# FEU-102-1_part4.net
KiCad netlist of a schematic drawn in Altium Designer
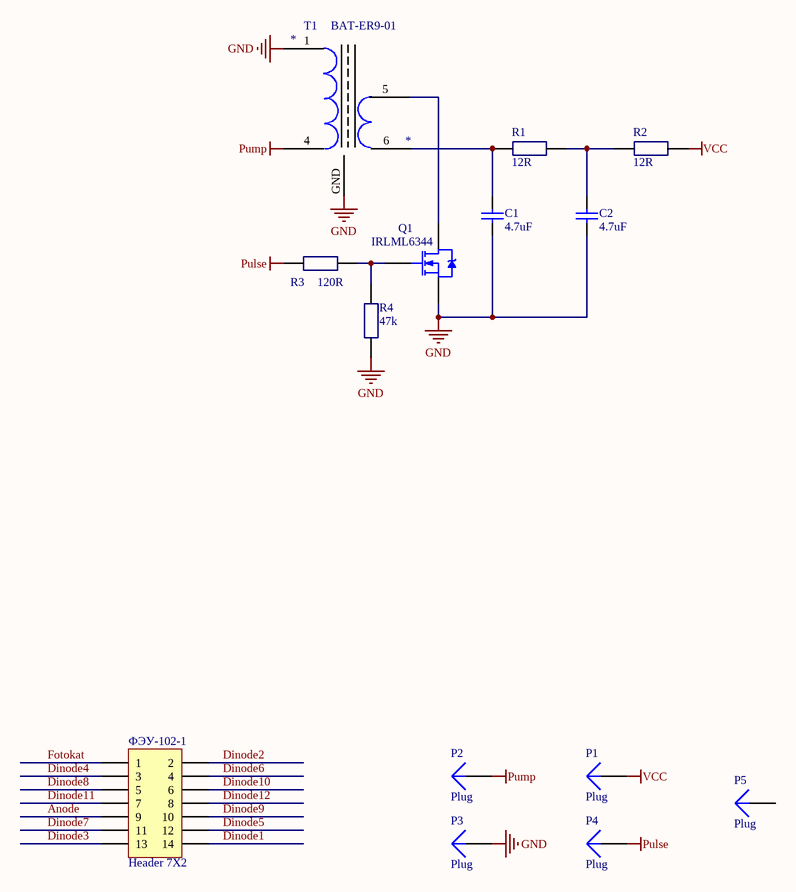
[diagram p0: FEU-102-1_part4.SchDoc]

(export (version "E")
  (design (tool "Eeschema 10.0.6"))
  (components
    (comp (ref "C1")
      (value "4.7uF")
      (footprint "Miscellaneous Devices:C1206")
      (description "Capacitor (Semiconductor SIM Model)")
      (fields (field (name "PUBLISHER") "Altium Limited"))
      (libsource (lib "Miscellaneous Devices") (part "Cap Semi"))
    )
    (comp (ref "C2")
      (value "4.7uF")
      (footprint "Miscellaneous Devices:C1206")
      (description "Capacitor (Semiconductor SIM Model)")
      (fields (field (name "PUBLISHER") "Altium Limited"))
      (libsource (lib "Miscellaneous Devices") (part "Cap Semi"))
    )
    (comp (ref "P1")
      (value "Plug")
      (footprint "PIN1")
      (fields (field (name "PUBLISHER") "Altium Limited"))
      (libsource (lib "Miscellaneous Connectors") (part "Plug"))
    )
    (comp (ref "P2")
      (value "Plug")
      (footprint "PIN1")
      (fields (field (name "PUBLISHER") "Altium Limited"))
      (libsource (lib "Miscellaneous Connectors") (part "Plug"))
    )
    (comp (ref "P3")
      (value "Plug")
      (footprint "PIN1")
      (fields (field (name "PUBLISHER") "Altium Limited"))
      (libsource (lib "Miscellaneous Connectors") (part "Plug"))
    )
    (comp (ref "P4")
      (value "Plug")
      (footprint "PIN1")
      (fields (field (name "PUBLISHER") "Altium Limited"))
      (libsource (lib "Miscellaneous Connectors") (part "Plug"))
    )
    (comp (ref "P5")
      (value "Plug")
      (footprint "PIN1")
      (fields (field (name "PUBLISHER") "Altium Limited"))
      (libsource (lib "Miscellaneous Connectors") (part "Plug"))
    )
    (comp (ref "Q1")
      (value "IRLML6344")
      (footprint "SOT-23_N")
      (description "HEXFET Power MOSFET")
      (fields (field (name "PUBLISHER") "Altium Limited"))
      (libsource (lib "IR Discrete MOSFET - Power") (part "IRLML2402"))
    )
    (comp (ref "R1")
      (value "12R")
      (footprint "1608[0603]_RES")
      (libsource (lib "Микрон-3") (part "Resistor 0805"))
    )
    (comp (ref "R2")
      (value "12R")
      (footprint "1608[0603]_RES")
      (libsource (lib "Микрон-3") (part "Resistor 0805"))
    )
    (comp (ref "R3")
      (value "120R")
      (footprint "1608[0603]_RES")
      (libsource (lib "Микрон-3") (part "Resistor 0805"))
    )
    (comp (ref "R4")
      (value "47k")
      (footprint "1608[0603]_RES")
      (libsource (lib "Микрон-3") (part "Resistor 0805"))
    )
    (comp (ref "T1")
      (value "BAT-ER9-01")
      (footprint "Epcos ER9.5/5")
      (libsource (lib "My SCH library") (part "Epcos ER9.5/5"))
    )
    (comp (ref "ФЭУ-102-1")
      (value "Header 7X2")
      (footprint "ФЭУ-102")
      (description "Header, 7-Pin, Dual row")
      (fields (field (name "PUBLISHER") "Altium Limited"))
      (libsource (lib "Miscellaneous Connectors") (part "Header 7X2"))
    )
  )
  (nets
    (net (code "1") (name "/Anode") (class "Default")
      (node (ref "ФЭУ-102-1") (pin "9") (pinfunction "9_9") (pintype "passive"))
    )
    (net (code "2") (name "/Dinode1") (class "Default")
      (node (ref "ФЭУ-102-1") (pin "14") (pinfunction "14_14") (pintype "passive"))
    )
    (net (code "3") (name "/Dinode2") (class "Default")
      (node (ref "ФЭУ-102-1") (pin "2") (pinfunction "2_2") (pintype "passive"))
    )
    (net (code "4") (name "/Dinode3") (class "Default")
      (node (ref "ФЭУ-102-1") (pin "13") (pinfunction "13_13") (pintype "passive"))
    )
    (net (code "5") (name "/Dinode4") (class "Default")
      (node (ref "ФЭУ-102-1") (pin "3") (pinfunction "3_3") (pintype "passive"))
    )
    (net (code "6") (name "/Dinode5") (class "Default")
      (node (ref "ФЭУ-102-1") (pin "12") (pinfunction "12_12") (pintype "passive"))
    )
    (net (code "7") (name "/Dinode6") (class "Default")
      (node (ref "ФЭУ-102-1") (pin "4") (pinfunction "4_4") (pintype "passive"))
    )
    (net (code "8") (name "/Dinode7") (class "Default")
      (node (ref "ФЭУ-102-1") (pin "11") (pinfunction "11_11") (pintype "passive"))
    )
    (net (code "9") (name "/Dinode8") (class "Default")
      (node (ref "ФЭУ-102-1") (pin "5") (pinfunction "5_5") (pintype "passive"))
    )
    (net (code "10") (name "/Dinode9") (class "Default")
      (node (ref "ФЭУ-102-1") (pin "10") (pinfunction "10_10") (pintype "passive"))
    )
    (net (code "11") (name "/Dinode10") (class "Default")
      (node (ref "ФЭУ-102-1") (pin "6") (pinfunction "6_6") (pintype "passive"))
    )
    (net (code "12") (name "/Dinode11") (class "Default")
      (node (ref "ФЭУ-102-1") (pin "7") (pinfunction "7_7") (pintype "passive"))
    )
    (net (code "13") (name "/Dinode12") (class "Default")
      (node (ref "ФЭУ-102-1") (pin "8") (pinfunction "8_8") (pintype "passive"))
    )
    (net (code "14") (name "/Fotokat") (class "Default")
      (node (ref "ФЭУ-102-1") (pin "1") (pinfunction "1_1") (pintype "passive"))
    )
    (net (code "15") (name "GND") (class "Default")
      (node (ref "C1") (pin "2") (pinfunction "2_2") (pintype "passive"))
      (node (ref "C2") (pin "2") (pinfunction "2_2") (pintype "passive"))
      (node (ref "P3") (pin "1") (pinfunction "1_1") (pintype "passive"))
      (node (ref "Q1") (pin "2") (pinfunction "S_2") (pintype "passive"))
      (node (ref "R4") (pin "1") (pinfunction "A_1") (pintype "passive"))
      (node (ref "T1") (pin "1") (pinfunction "1_1") (pintype "passive"))
      (node (ref "T1") (pin "GND") (pinfunction "GND_GND") (pintype "passive"))
    )
    (net (code "16") (name "Net-(Q1-D)") (class "Default")
      (node (ref "Q1") (pin "3") (pinfunction "D_3") (pintype "passive"))
      (node (ref "T1") (pin "5") (pinfunction "5_5") (pintype "passive"))
    )
    (net (code "17") (name "Net-(Q1-G)") (class "Default")
      (node (ref "Q1") (pin "1") (pinfunction "G_1") (pintype "passive"))
      (node (ref "R3") (pin "1") (pinfunction "A_1") (pintype "passive"))
      (node (ref "R4") (pin "2") (pinfunction "2_2") (pintype "passive"))
    )
    (net (code "18") (name "Net-(R1-A)") (class "Default")
      (node (ref "C1") (pin "1") (pinfunction "1_1") (pintype "passive"))
      (node (ref "R1") (pin "1") (pinfunction "A_1") (pintype "passive"))
      (node (ref "T1") (pin "6") (pintype "passive"))
    )
    (net (code "19") (name "Net-(R2-A)") (class "Default")
      (node (ref "C2") (pin "1") (pinfunction "1_1") (pintype "passive"))
      (node (ref "R1") (pin "2") (pinfunction "2_2") (pintype "passive"))
      (node (ref "R2") (pin "1") (pinfunction "A_1") (pintype "passive"))
    )
    (net (code "20") (name "Pulse") (class "Default")
      (node (ref "P4") (pin "1") (pinfunction "1_1") (pintype "passive"))
      (node (ref "R3") (pin "2") (pinfunction "2_2") (pintype "passive"))
    )
    (net (code "21") (name "Pump") (class "Default")
      (node (ref "P2") (pin "1") (pinfunction "1_1") (pintype "passive"))
      (node (ref "T1") (pin "4") (pinfunction "4_4") (pintype "passive"))
    )
    (net (code "22") (name "VCC") (class "Default")
      (node (ref "P1") (pin "1") (pinfunction "1_1") (pintype "passive"))
      (node (ref "R2") (pin "2") (pinfunction "2_2") (pintype "passive"))
    )
    (net (code "23") (name "unconnected-(P5-Pad1)") (class "Default")
      (node (ref "P5") (pin "1") (pinfunction "1_1") (pintype "passive"))
    )
  )
)
